# wifi_board.net
KiCad netlist of a schematic drawn in EAGLE
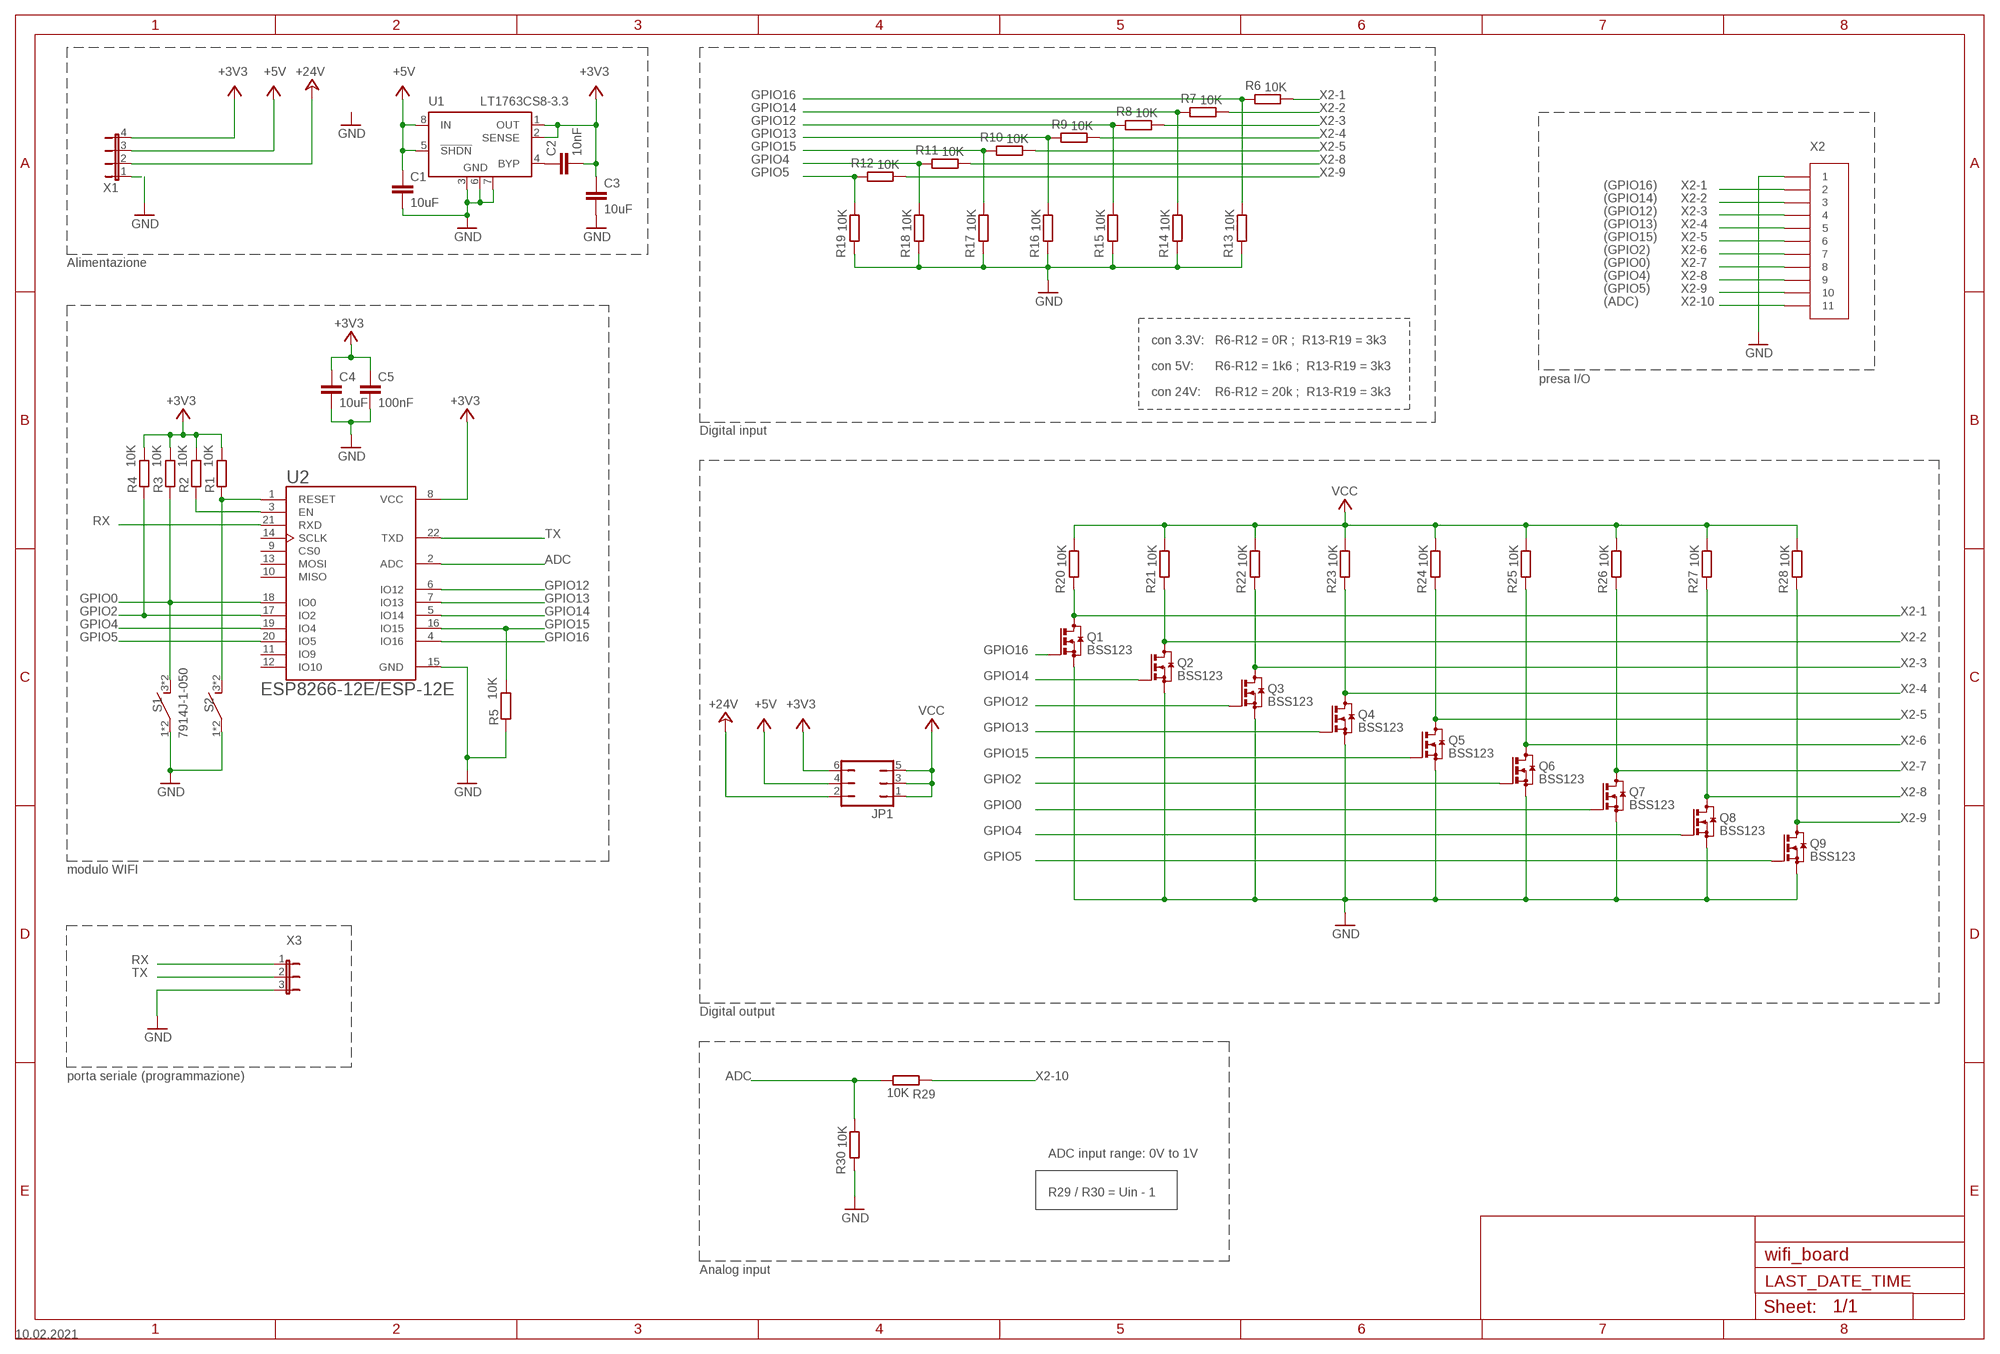
[diagram p0: schematic, sheet 1]

(export (version "E")
  (design (tool "Eeschema 10.0.6"))
  (components
    (comp (ref "C1")
      (value "10uF")
      (footprint "eagle-import:C0805")
      (libsource (lib "eagle-import") (part "C-EUC0805"))
    )
    (comp (ref "C2")
      (value "10nF")
      (footprint "eagle-import:C0805")
      (libsource (lib "eagle-import") (part "C-EUC0805"))
    )
    (comp (ref "C3")
      (value "10uF")
      (footprint "eagle-import:C0805")
      (libsource (lib "eagle-import") (part "C-EUC0805"))
    )
    (comp (ref "C4")
      (value "10uF")
      (footprint "eagle-import:C0805")
      (libsource (lib "eagle-import") (part "C-EUC0805"))
    )
    (comp (ref "C5")
      (value "100nF")
      (footprint "eagle-import:C0805")
      (libsource (lib "eagle-import") (part "C-EUC0805"))
    )
    (comp (ref "JP1")
      (value "JP3Q")
      (footprint "eagle-import:JP3Q")
      (libsource (lib "eagle-import") (part "JP3Q"))
    )
    (comp (ref "Q1")
      (value "BSS123")
      (footprint "eagle-import:SOT23")
      (libsource (lib "eagle-import") (part "BSS123"))
    )
    (comp (ref "Q2")
      (value "BSS123")
      (footprint "eagle-import:SOT23")
      (libsource (lib "eagle-import") (part "BSS123"))
    )
    (comp (ref "Q3")
      (value "BSS123")
      (footprint "eagle-import:SOT23")
      (libsource (lib "eagle-import") (part "BSS123"))
    )
    (comp (ref "Q4")
      (value "BSS123")
      (footprint "eagle-import:SOT23")
      (libsource (lib "eagle-import") (part "BSS123"))
    )
    (comp (ref "Q5")
      (value "BSS123")
      (footprint "eagle-import:SOT23")
      (libsource (lib "eagle-import") (part "BSS123"))
    )
    (comp (ref "Q6")
      (value "BSS123")
      (footprint "eagle-import:SOT23")
      (libsource (lib "eagle-import") (part "BSS123"))
    )
    (comp (ref "Q7")
      (value "BSS123")
      (footprint "eagle-import:SOT23")
      (libsource (lib "eagle-import") (part "BSS123"))
    )
    (comp (ref "Q8")
      (value "BSS123")
      (footprint "eagle-import:SOT23")
      (libsource (lib "eagle-import") (part "BSS123"))
    )
    (comp (ref "Q9")
      (value "BSS123")
      (footprint "eagle-import:SOT23")
      (libsource (lib "eagle-import") (part "BSS123"))
    )
    (comp (ref "R1")
      (value "10K")
      (footprint "eagle-import:R0805")
      (libsource (lib "eagle-import") (part "R-EU_R0805"))
    )
    (comp (ref "R2")
      (value "10K")
      (footprint "eagle-import:R0805")
      (libsource (lib "eagle-import") (part "R-EU_R0805"))
    )
    (comp (ref "R3")
      (value "10K")
      (footprint "eagle-import:R0805")
      (libsource (lib "eagle-import") (part "R-EU_R0805"))
    )
    (comp (ref "R4")
      (value "10K")
      (footprint "eagle-import:R0805")
      (libsource (lib "eagle-import") (part "R-EU_R0805"))
    )
    (comp (ref "R5")
      (value "10K")
      (footprint "eagle-import:R0805")
      (libsource (lib "eagle-import") (part "R-EU_R0805"))
    )
    (comp (ref "R6")
      (value "10K")
      (footprint "eagle-import:R0805")
      (libsource (lib "eagle-import") (part "R-EU_R0805"))
    )
    (comp (ref "R7")
      (value "10K")
      (footprint "eagle-import:R0805")
      (libsource (lib "eagle-import") (part "R-EU_R0805"))
    )
    (comp (ref "R8")
      (value "10K")
      (footprint "eagle-import:R0805")
      (libsource (lib "eagle-import") (part "R-EU_R0805"))
    )
    (comp (ref "R9")
      (value "10K")
      (footprint "eagle-import:R0805")
      (libsource (lib "eagle-import") (part "R-EU_R0805"))
    )
    (comp (ref "R10")
      (value "10K")
      (footprint "eagle-import:R0805")
      (libsource (lib "eagle-import") (part "R-EU_R0805"))
    )
    (comp (ref "R11")
      (value "10K")
      (footprint "eagle-import:R0805")
      (libsource (lib "eagle-import") (part "R-EU_R0805"))
    )
    (comp (ref "R12")
      (value "10K")
      (footprint "eagle-import:R0805")
      (libsource (lib "eagle-import") (part "R-EU_R0805"))
    )
    (comp (ref "R13")
      (value "10K")
      (footprint "eagle-import:R0805")
      (libsource (lib "eagle-import") (part "R-EU_R0805"))
    )
    (comp (ref "R14")
      (value "10K")
      (footprint "eagle-import:R0805")
      (libsource (lib "eagle-import") (part "R-EU_R0805"))
    )
    (comp (ref "R15")
      (value "10K")
      (footprint "eagle-import:R0805")
      (libsource (lib "eagle-import") (part "R-EU_R0805"))
    )
    (comp (ref "R16")
      (value "10K")
      (footprint "eagle-import:R0805")
      (libsource (lib "eagle-import") (part "R-EU_R0805"))
    )
    (comp (ref "R17")
      (value "10K")
      (footprint "eagle-import:R0805")
      (libsource (lib "eagle-import") (part "R-EU_R0805"))
    )
    (comp (ref "R18")
      (value "10K")
      (footprint "eagle-import:R0805")
      (libsource (lib "eagle-import") (part "R-EU_R0805"))
    )
    (comp (ref "R19")
      (value "10K")
      (footprint "eagle-import:R0805")
      (libsource (lib "eagle-import") (part "R-EU_R0805"))
    )
    (comp (ref "R20")
      (value "10K")
      (footprint "eagle-import:R0805")
      (libsource (lib "eagle-import") (part "R-EU_R0805"))
    )
    (comp (ref "R21")
      (value "10K")
      (footprint "eagle-import:R0805")
      (libsource (lib "eagle-import") (part "R-EU_R0805"))
    )
    (comp (ref "R22")
      (value "10K")
      (footprint "eagle-import:R0805")
      (libsource (lib "eagle-import") (part "R-EU_R0805"))
    )
    (comp (ref "R23")
      (value "10K")
      (footprint "eagle-import:R0805")
      (libsource (lib "eagle-import") (part "R-EU_R0805"))
    )
    (comp (ref "R24")
      (value "10K")
      (footprint "eagle-import:R0805")
      (libsource (lib "eagle-import") (part "R-EU_R0805"))
    )
    (comp (ref "R25")
      (value "10K")
      (footprint "eagle-import:R0805")
      (libsource (lib "eagle-import") (part "R-EU_R0805"))
    )
    (comp (ref "R26")
      (value "10K")
      (footprint "eagle-import:R0805")
      (libsource (lib "eagle-import") (part "R-EU_R0805"))
    )
    (comp (ref "R27")
      (value "10K")
      (footprint "eagle-import:R0805")
      (libsource (lib "eagle-import") (part "R-EU_R0805"))
    )
    (comp (ref "R28")
      (value "10K")
      (footprint "eagle-import:R0805")
      (libsource (lib "eagle-import") (part "R-EU_R0805"))
    )
    (comp (ref "R29")
      (value "10K")
      (footprint "eagle-import:R0805")
      (libsource (lib "eagle-import") (part "R-EU_R0805"))
    )
    (comp (ref "R30")
      (value "10K")
      (footprint "eagle-import:R0805")
      (libsource (lib "eagle-import") (part "R-EU_R0805"))
    )
    (comp (ref "S1")
      (value "7914J-1-050")
      (footprint "eagle-import:7914J1000E")
      (fields (field (name "MF") "Bourns"))
      (libsource (lib "eagle-import") (part "7914J-1-050"))
    )
    (comp (ref "S2")
      (value "7914J-1-050")
      (footprint "eagle-import:7914J1000E")
      (fields (field (name "MF") "Bourns"))
      (libsource (lib "eagle-import") (part "7914J-1-050"))
    )
    (comp (ref "U1")
      (value "LT1763CS8-3.3")
      (footprint "eagle-import:SOIC8")
      (libsource (lib "eagle-import") (part "LT1763CS8-3.3"))
    )
    (comp (ref "U2")
      (value "ESP8266-12E/ESP-12E")
      (footprint "eagle-import:XCVR_ESP8266-12E_ESP-12E")
      (fields (field (name "MF") "AI-Thinker"))
      (libsource (lib "eagle-import") (part "ESP8266-12E/ESP-12E"))
    )
    (comp (ref "X1")
      (value "JP4E")
      (footprint "eagle-import:JP4")
      (libsource (lib "eagle-import") (part "JP4E"))
    )
    (comp (ref "X2")
      (value "X11P")
      (footprint "eagle-import:X11P")
      (libsource (lib "eagle-import") (part "X11P"))
    )
    (comp (ref "X3")
      (value "JP2E")
      (footprint "eagle-import:JP2")
      (libsource (lib "eagle-import") (part "JP2E"))
    )
  )
  (nets
    (net (code "1") (name "+3V3") (class "Default")
      (node (ref "C2") (pin "2") (pinfunction "2_2") (pintype "passive"))
      (node (ref "C3") (pin "1") (pinfunction "1_1") (pintype "passive"))
      (node (ref "C4") (pin "1") (pinfunction "1_1") (pintype "passive"))
      (node (ref "C5") (pin "1") (pinfunction "1_1") (pintype "passive"))
      (node (ref "JP1") (pin "6") (pinfunction "6_6") (pintype "passive"))
      (node (ref "R1") (pin "2") (pinfunction "2_2") (pintype "passive"))
      (node (ref "R2") (pin "2") (pinfunction "2_2") (pintype "passive"))
      (node (ref "R3") (pin "2") (pinfunction "2_2") (pintype "passive"))
      (node (ref "R4") (pin "2") (pinfunction "2_2") (pintype "passive"))
      (node (ref "U1") (pin "1") (pinfunction "OUT_1") (pintype "passive"))
      (node (ref "U1") (pin "2") (pinfunction "SENSE_2") (pintype "input"))
      (node (ref "U2") (pin "8") (pinfunction "VCC_8") (pintype "power_in"))
      (node (ref "X1") (pin "4") (pinfunction "4_4") (pintype "passive"))
    )
    (net (code "2") (name "+5V") (class "Default")
      (node (ref "C1") (pin "1") (pinfunction "1_1") (pintype "passive"))
      (node (ref "JP1") (pin "4") (pinfunction "4_4") (pintype "passive"))
      (node (ref "U1") (pin "5") (pinfunction "~{SHDN}_5") (pintype "input"))
      (node (ref "U1") (pin "8") (pinfunction "IN_8") (pintype "input"))
      (node (ref "X1") (pin "3") (pinfunction "3_3") (pintype "passive"))
    )
    (net (code "3") (name "+24V") (class "Default")
      (node (ref "JP1") (pin "2") (pinfunction "2_2") (pintype "passive"))
      (node (ref "X1") (pin "2") (pinfunction "2_2") (pintype "passive"))
    )
    (net (code "4") (name "/ADC") (class "Default")
      (node (ref "R29") (pin "1") (pinfunction "1_1") (pintype "passive"))
      (node (ref "R30") (pin "1") (pinfunction "1_1") (pintype "passive"))
      (node (ref "U2") (pin "2") (pinfunction "ADC_2") (pintype "passive"))
    )
    (net (code "5") (name "/GPIO0") (class "Default")
      (node (ref "Q7") (pin "1") (pinfunction "G_1") (pintype "passive"))
      (node (ref "R3") (pin "1") (pinfunction "1_1") (pintype "passive"))
      (node (ref "S1") (pin "3") (pinfunction "2_3") (pintype "bidirectional"))
      (node (ref "S1") (pin "4") (pinfunction "2_4") (pintype "bidirectional"))
      (node (ref "U2") (pin "18") (pinfunction "IO0_18") (pintype "bidirectional"))
    )
    (net (code "6") (name "/GPIO2") (class "Default")
      (node (ref "Q6") (pin "1") (pinfunction "G_1") (pintype "passive"))
      (node (ref "R4") (pin "1") (pinfunction "1_1") (pintype "passive"))
      (node (ref "U2") (pin "17") (pinfunction "IO2_17") (pintype "bidirectional"))
    )
    (net (code "7") (name "/GPIO4") (class "Default")
      (node (ref "Q8") (pin "1") (pinfunction "G_1") (pintype "passive"))
      (node (ref "R11") (pin "2") (pinfunction "2_2") (pintype "passive"))
      (node (ref "R18") (pin "1") (pinfunction "1_1") (pintype "passive"))
      (node (ref "U2") (pin "19") (pinfunction "IO4_19") (pintype "bidirectional"))
    )
    (net (code "8") (name "/GPIO5") (class "Default")
      (node (ref "Q9") (pin "1") (pinfunction "G_1") (pintype "passive"))
      (node (ref "R12") (pin "2") (pinfunction "2_2") (pintype "passive"))
      (node (ref "R19") (pin "1") (pinfunction "1_1") (pintype "passive"))
      (node (ref "U2") (pin "20") (pinfunction "IO5_20") (pintype "bidirectional"))
    )
    (net (code "9") (name "/GPIO12") (class "Default")
      (node (ref "Q3") (pin "1") (pinfunction "G_1") (pintype "passive"))
      (node (ref "R15") (pin "1") (pinfunction "1_1") (pintype "passive"))
      (node (ref "R8") (pin "2") (pinfunction "2_2") (pintype "passive"))
      (node (ref "U2") (pin "6") (pinfunction "IO12_6") (pintype "bidirectional"))
    )
    (net (code "10") (name "/GPIO13") (class "Default")
      (node (ref "Q4") (pin "1") (pinfunction "G_1") (pintype "passive"))
      (node (ref "R16") (pin "1") (pinfunction "1_1") (pintype "passive"))
      (node (ref "R9") (pin "2") (pinfunction "2_2") (pintype "passive"))
      (node (ref "U2") (pin "7") (pinfunction "IO13_7") (pintype "bidirectional"))
    )
    (net (code "11") (name "/GPIO14") (class "Default")
      (node (ref "Q2") (pin "1") (pinfunction "G_1") (pintype "passive"))
      (node (ref "R14") (pin "1") (pinfunction "1_1") (pintype "passive"))
      (node (ref "R7") (pin "2") (pinfunction "2_2") (pintype "passive"))
      (node (ref "U2") (pin "5") (pinfunction "IO14_5") (pintype "bidirectional"))
    )
    (net (code "12") (name "/GPIO15") (class "Default")
      (node (ref "Q5") (pin "1") (pinfunction "G_1") (pintype "passive"))
      (node (ref "R10") (pin "2") (pinfunction "2_2") (pintype "passive"))
      (node (ref "R17") (pin "1") (pinfunction "1_1") (pintype "passive"))
      (node (ref "R5") (pin "2") (pinfunction "2_2") (pintype "passive"))
      (node (ref "U2") (pin "16") (pinfunction "IO15_16") (pintype "bidirectional"))
    )
    (net (code "13") (name "/GPIO16") (class "Default")
      (node (ref "Q1") (pin "1") (pinfunction "G_1") (pintype "passive"))
      (node (ref "R13") (pin "1") (pinfunction "1_1") (pintype "passive"))
      (node (ref "R6") (pin "2") (pinfunction "2_2") (pintype "passive"))
      (node (ref "U2") (pin "4") (pinfunction "IO16_4") (pintype "bidirectional"))
    )
    (net (code "14") (name "/RX") (class "Default")
      (node (ref "U2") (pin "21") (pinfunction "RXD_21") (pintype "input"))
      (node (ref "X3") (pin "1") (pinfunction "1_1") (pintype "passive"))
    )
    (net (code "15") (name "/TX") (class "Default")
      (node (ref "U2") (pin "22") (pinfunction "TXD_22") (pintype "output"))
      (node (ref "X3") (pin "2") (pinfunction "2_2") (pintype "passive"))
    )
    (net (code "16") (name "/X2-1") (class "Default")
      (node (ref "Q1") (pin "3") (pinfunction "D_3") (pintype "passive"))
      (node (ref "R20") (pin "2") (pinfunction "2_2") (pintype "passive"))
      (node (ref "R6") (pin "1") (pinfunction "1_1") (pintype "passive"))
      (node (ref "X2") (pin "2") (pinfunction "2_2") (pintype "bidirectional"))
    )
    (net (code "17") (name "/X2-2") (class "Default")
      (node (ref "Q2") (pin "3") (pinfunction "D_3") (pintype "passive"))
      (node (ref "R21") (pin "2") (pinfunction "2_2") (pintype "passive"))
      (node (ref "R7") (pin "1") (pinfunction "1_1") (pintype "passive"))
      (node (ref "X2") (pin "3") (pinfunction "3_3") (pintype "bidirectional"))
    )
    (net (code "18") (name "/X2-3") (class "Default")
      (node (ref "Q3") (pin "3") (pinfunction "D_3") (pintype "passive"))
      (node (ref "R22") (pin "2") (pinfunction "2_2") (pintype "passive"))
      (node (ref "R8") (pin "1") (pinfunction "1_1") (pintype "passive"))
      (node (ref "X2") (pin "4") (pinfunction "4_4") (pintype "bidirectional"))
    )
    (net (code "19") (name "/X2-4") (class "Default")
      (node (ref "Q4") (pin "3") (pinfunction "D_3") (pintype "passive"))
      (node (ref "R23") (pin "2") (pinfunction "2_2") (pintype "passive"))
      (node (ref "R9") (pin "1") (pinfunction "1_1") (pintype "passive"))
      (node (ref "X2") (pin "5") (pinfunction "5_5") (pintype "bidirectional"))
    )
    (net (code "20") (name "/X2-5") (class "Default")
      (node (ref "Q5") (pin "3") (pinfunction "D_3") (pintype "passive"))
      (node (ref "R10") (pin "1") (pinfunction "1_1") (pintype "passive"))
      (node (ref "R24") (pin "2") (pinfunction "2_2") (pintype "passive"))
      (node (ref "X2") (pin "6") (pinfunction "6_6") (pintype "bidirectional"))
    )
    (net (code "21") (name "/X2-6") (class "Default")
      (node (ref "Q6") (pin "3") (pinfunction "D_3") (pintype "passive"))
      (node (ref "R25") (pin "2") (pinfunction "2_2") (pintype "passive"))
      (node (ref "X2") (pin "7") (pinfunction "7_7") (pintype "bidirectional"))
    )
    (net (code "22") (name "/X2-7") (class "Default")
      (node (ref "Q7") (pin "3") (pinfunction "D_3") (pintype "passive"))
      (node (ref "R26") (pin "2") (pinfunction "2_2") (pintype "passive"))
      (node (ref "X2") (pin "8") (pinfunction "8_8") (pintype "bidirectional"))
    )
    (net (code "23") (name "/X2-8") (class "Default")
      (node (ref "Q8") (pin "3") (pinfunction "D_3") (pintype "passive"))
      (node (ref "R11") (pin "1") (pinfunction "1_1") (pintype "passive"))
      (node (ref "R27") (pin "2") (pinfunction "2_2") (pintype "passive"))
      (node (ref "X2") (pin "9") (pinfunction "9_9") (pintype "bidirectional"))
    )
    (net (code "24") (name "/X2-9") (class "Default")
      (node (ref "Q9") (pin "3") (pinfunction "D_3") (pintype "passive"))
      (node (ref "R12") (pin "1") (pinfunction "1_1") (pintype "passive"))
      (node (ref "R28") (pin "2") (pinfunction "2_2") (pintype "passive"))
      (node (ref "X2") (pin "10") (pinfunction "10_10") (pintype "bidirectional"))
    )
    (net (code "25") (name "/X2-10") (class "Default")
      (node (ref "R29") (pin "2") (pinfunction "2_2") (pintype "passive"))
      (node (ref "X2") (pin "11") (pinfunction "11_11") (pintype "bidirectional"))
    )
    (net (code "26") (name "GND") (class "Default")
      (node (ref "C1") (pin "2") (pinfunction "2_2") (pintype "passive"))
      (node (ref "C3") (pin "2") (pinfunction "2_2") (pintype "passive"))
      (node (ref "C4") (pin "2") (pinfunction "2_2") (pintype "passive"))
      (node (ref "C5") (pin "2") (pinfunction "2_2") (pintype "passive"))
      (node (ref "Q1") (pin "2") (pinfunction "S_2") (pintype "passive"))
      (node (ref "Q2") (pin "2") (pinfunction "S_2") (pintype "passive"))
      (node (ref "Q3") (pin "2") (pinfunction "S_2") (pintype "passive"))
      (node (ref "Q4") (pin "2") (pinfunction "S_2") (pintype "passive"))
      (node (ref "Q5") (pin "2") (pinfunction "S_2") (pintype "passive"))
      (node (ref "Q6") (pin "2") (pinfunction "S_2") (pintype "passive"))
      (node (ref "Q7") (pin "2") (pinfunction "S_2") (pintype "passive"))
      (node (ref "Q8") (pin "2") (pinfunction "S_2") (pintype "passive"))
      (node (ref "Q9") (pin "2") (pinfunction "S_2") (pintype "passive"))
      (node (ref "R13") (pin "2") (pinfunction "2_2") (pintype "passive"))
      (node (ref "R14") (pin "2") (pinfunction "2_2") (pintype "passive"))
      (node (ref "R15") (pin "2") (pinfunction "2_2") (pintype "passive"))
      (node (ref "R16") (pin "2") (pinfunction "2_2") (pintype "passive"))
      (node (ref "R17") (pin "2") (pinfunction "2_2") (pintype "passive"))
      (node (ref "R18") (pin "2") (pinfunction "2_2") (pintype "passive"))
      (node (ref "R19") (pin "2") (pinfunction "2_2") (pintype "passive"))
      (node (ref "R30") (pin "2") (pinfunction "2_2") (pintype "passive"))
      (node (ref "R5") (pin "1") (pinfunction "1_1") (pintype "passive"))
      (node (ref "S1") (pin "1") (pinfunction "1_1") (pintype "bidirectional"))
      (node (ref "S1") (pin "2") (pinfunction "1_2") (pintype "bidirectional"))
      (node (ref "S2") (pin "1") (pinfunction "1_1") (pintype "bidirectional"))
      (node (ref "S2") (pin "2") (pinfunction "1_2") (pintype "bidirectional"))
      (node (ref "U1") (pin "3") (pinfunction "GND_3") (pintype "power_in"))
      (node (ref "U1") (pin "6") (pinfunction "GND_6") (pintype "power_in"))
      (node (ref "U1") (pin "7") (pinfunction "GND_7") (pintype "power_in"))
      (node (ref "U2") (pin "15") (pinfunction "GND_15") (pintype "power_in"))
      (node (ref "X1") (pin "1") (pinfunction "1_1") (pintype "passive"))
      (node (ref "X2") (pin "1") (pinfunction "1_1") (pintype "bidirectional"))
      (node (ref "X3") (pin "3") (pinfunction "3_3") (pintype "passive"))
    )
    (net (code "27") (name "Net-(U1-BYP)") (class "Default")
      (node (ref "C2") (pin "1") (pinfunction "1_1") (pintype "passive"))
      (node (ref "U1") (pin "4") (pinfunction "BYP_4") (pintype "input"))
    )
    (net (code "28") (name "Net-(U2-EN)") (class "Default")
      (node (ref "R2") (pin "1") (pinfunction "1_1") (pintype "passive"))
      (node (ref "U2") (pin "3") (pinfunction "EN_3") (pintype "input"))
    )
    (net (code "29") (name "Net-(U2-RESET)") (class "Default")
      (node (ref "R1") (pin "1") (pinfunction "1_1") (pintype "passive"))
      (node (ref "S2") (pin "3") (pinfunction "2_3") (pintype "bidirectional"))
      (node (ref "S2") (pin "4") (pinfunction "2_4") (pintype "bidirectional"))
      (node (ref "U2") (pin "1") (pinfunction "RESET_1") (pintype "input"))
    )
    (net (code "30") (name "VCC") (class "Default")
      (node (ref "JP1") (pin "1") (pinfunction "1_1") (pintype "passive"))
      (node (ref "JP1") (pin "3") (pinfunction "3_3") (pintype "passive"))
      (node (ref "JP1") (pin "5") (pinfunction "5_5") (pintype "passive"))
      (node (ref "R20") (pin "1") (pinfunction "1_1") (pintype "passive"))
      (node (ref "R21") (pin "1") (pinfunction "1_1") (pintype "passive"))
      (node (ref "R22") (pin "1") (pinfunction "1_1") (pintype "passive"))
      (node (ref "R23") (pin "1") (pinfunction "1_1") (pintype "passive"))
      (node (ref "R24") (pin "1") (pinfunction "1_1") (pintype "passive"))
      (node (ref "R25") (pin "1") (pinfunction "1_1") (pintype "passive"))
      (node (ref "R26") (pin "1") (pinfunction "1_1") (pintype "passive"))
      (node (ref "R27") (pin "1") (pinfunction "1_1") (pintype "passive"))
      (node (ref "R28") (pin "1") (pinfunction "1_1") (pintype "passive"))
    )
    (net (code "31") (name "unconnected-(U2-CS0-Pad9)") (class "Default")
      (node (ref "U2") (pin "9") (pinfunction "CS0_9") (pintype "input"))
    )
    (net (code "32") (name "unconnected-(U2-IO9-Pad11)") (class "Default")
      (node (ref "U2") (pin "11") (pinfunction "IO9_11") (pintype "bidirectional"))
    )
    (net (code "33") (name "unconnected-(U2-IO10-Pad12)") (class "Default")
      (node (ref "U2") (pin "12") (pinfunction "IO10_12") (pintype "bidirectional"))
    )
    (net (code "34") (name "unconnected-(U2-MISO-Pad10)") (class "Default")
      (node (ref "U2") (pin "10") (pinfunction "MISO_10") (pintype "bidirectional"))
    )
    (net (code "35") (name "unconnected-(U2-MOSI-Pad13)") (class "Default")
      (node (ref "U2") (pin "13") (pinfunction "MOSI_13") (pintype "bidirectional"))
    )
    (net (code "36") (name "unconnected-(U2-SCLK-Pad14)") (class "Default")
      (node (ref "U2") (pin "14") (pinfunction "SCLK_14") (pintype "input"))
    )
  )
)
